# Interfacenopanda.net
KiCad netlist of a schematic drawn in EAGLE
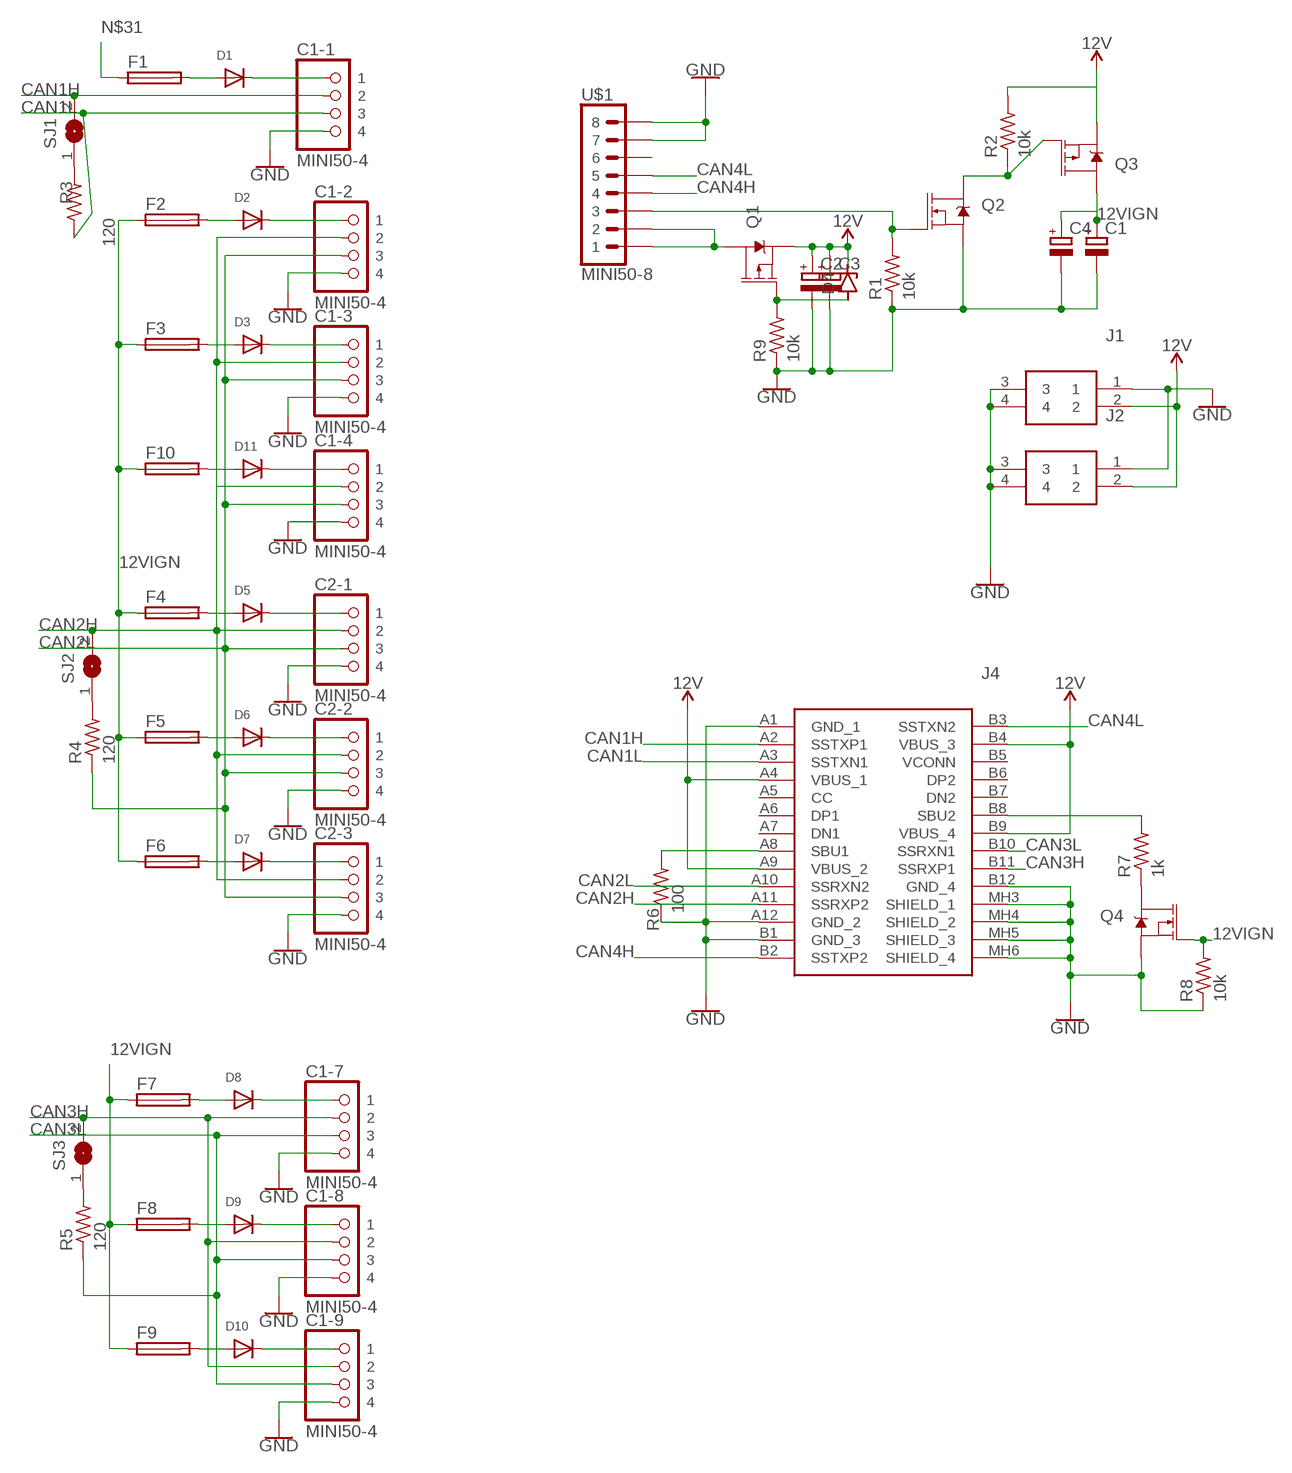
[diagram p0: schematic, sheet 1]

(export (version "E")
  (design (tool "Eeschema 10.0.6"))
  (components
    (comp (ref "C1")
      (value "CPOL-EU153CLV-1010")
      (footprint "eagle-import:153CLV-1010")
      (libsource (lib "eagle-import") (part "CPOL-EU153CLV-1010"))
    )
    (comp (ref "C1-1")
      (value "MINI50-4")
      (footprint "eagle-import:MINI50")
      (libsource (lib "eagle-import") (part "MINI50-4"))
    )
    (comp (ref "C1-2")
      (value "MINI50-4")
      (footprint "eagle-import:MINI50")
      (libsource (lib "eagle-import") (part "MINI50-4"))
    )
    (comp (ref "C1-3")
      (value "MINI50-4")
      (footprint "eagle-import:MINI50")
      (libsource (lib "eagle-import") (part "MINI50-4"))
    )
    (comp (ref "C1-4")
      (value "MINI50-4")
      (footprint "eagle-import:MINI50")
      (libsource (lib "eagle-import") (part "MINI50-4"))
    )
    (comp (ref "C1-7")
      (value "MINI50-4")
      (footprint "eagle-import:MINI50")
      (libsource (lib "eagle-import") (part "MINI50-4"))
    )
    (comp (ref "C1-8")
      (value "MINI50-4")
      (footprint "eagle-import:MINI50")
      (libsource (lib "eagle-import") (part "MINI50-4"))
    )
    (comp (ref "C1-9")
      (value "MINI50-4")
      (footprint "eagle-import:MINI50")
      (libsource (lib "eagle-import") (part "MINI50-4"))
    )
    (comp (ref "C2")
      (value "CPOL-EU153CLV-1010")
      (footprint "eagle-import:153CLV-1010")
      (libsource (lib "eagle-import") (part "CPOL-EU153CLV-1010"))
    )
    (comp (ref "C2-1")
      (value "MINI50-4")
      (footprint "eagle-import:MINI50")
      (libsource (lib "eagle-import") (part "MINI50-4"))
    )
    (comp (ref "C2-2")
      (value "MINI50-4")
      (footprint "eagle-import:MINI50")
      (libsource (lib "eagle-import") (part "MINI50-4"))
    )
    (comp (ref "C2-3")
      (value "MINI50-4")
      (footprint "eagle-import:MINI50")
      (libsource (lib "eagle-import") (part "MINI50-4"))
    )
    (comp (ref "C3")
      (value "CPOL-EU153CLV-0505")
      (footprint "eagle-import:153CLV-0505")
      (libsource (lib "eagle-import") (part "CPOL-EU153CLV-0505"))
    )
    (comp (ref "C4")
      (value "CPOL-EU153CLV-0505")
      (footprint "eagle-import:153CLV-0505")
      (libsource (lib "eagle-import") (part "CPOL-EU153CLV-0505"))
    )
    (comp (ref "D1")
      (value "DIODESOD-323F")
      (footprint "eagle-import:SOD-323F")
      (libsource (lib "eagle-import") (part "DIODESOD-323F"))
    )
    (comp (ref "D2")
      (value "DIODESOD-323F")
      (footprint "eagle-import:SOD-323F")
      (libsource (lib "eagle-import") (part "DIODESOD-323F"))
    )
    (comp (ref "D3")
      (value "DIODESOD-323F")
      (footprint "eagle-import:SOD-323F")
      (libsource (lib "eagle-import") (part "DIODESOD-323F"))
    )
    (comp (ref "D4")
      (value "ZENER_DO-219-AB(SOD123F)")
      (footprint "eagle-import:SODFL3718X115")
      (libsource (lib "eagle-import") (part "ZENERDO-219-AB(SOD123F)_"))
    )
    (comp (ref "D5")
      (value "DIODESOD-323F")
      (footprint "eagle-import:SOD-323F")
      (libsource (lib "eagle-import") (part "DIODESOD-323F"))
    )
    (comp (ref "D6")
      (value "DIODESOD-323F")
      (footprint "eagle-import:SOD-323F")
      (libsource (lib "eagle-import") (part "DIODESOD-323F"))
    )
    (comp (ref "D7")
      (value "DIODESOD-323F")
      (footprint "eagle-import:SOD-323F")
      (libsource (lib "eagle-import") (part "DIODESOD-323F"))
    )
    (comp (ref "D8")
      (value "DIODESOD-323F")
      (footprint "eagle-import:SOD-323F")
      (libsource (lib "eagle-import") (part "DIODESOD-323F"))
    )
    (comp (ref "D9")
      (value "DIODESOD-323F")
      (footprint "eagle-import:SOD-323F")
      (libsource (lib "eagle-import") (part "DIODESOD-323F"))
    )
    (comp (ref "D10")
      (value "DIODESOD-323F")
      (footprint "eagle-import:SOD-323F")
      (libsource (lib "eagle-import") (part "DIODESOD-323F"))
    )
    (comp (ref "D11")
      (value "DIODESOD-323F")
      (footprint "eagle-import:SOD-323F")
      (libsource (lib "eagle-import") (part "DIODESOD-323F"))
    )
    (comp (ref "F1")
      (value "FUSE_CHIP-1206(3216-METRIC)")
      (footprint "eagle-import:FUSC3215X82N")
      (libsource (lib "eagle-import") (part "FUSECHIP-1206(3216-METRIC)_"))
    )
    (comp (ref "F2")
      (value "FUSE_CHIP-1206(3216-METRIC)")
      (footprint "eagle-import:FUSC3215X82N")
      (libsource (lib "eagle-import") (part "FUSECHIP-1206(3216-METRIC)_"))
    )
    (comp (ref "F3")
      (value "FUSE_CHIP-1206(3216-METRIC)")
      (footprint "eagle-import:FUSC3215X82N")
      (libsource (lib "eagle-import") (part "FUSECHIP-1206(3216-METRIC)_"))
    )
    (comp (ref "F4")
      (value "FUSE_CHIP-1206(3216-METRIC)")
      (footprint "eagle-import:FUSC3215X82N")
      (libsource (lib "eagle-import") (part "FUSECHIP-1206(3216-METRIC)_"))
    )
    (comp (ref "F5")
      (value "FUSE_CHIP-1206(3216-METRIC)")
      (footprint "eagle-import:FUSC3215X82N")
      (libsource (lib "eagle-import") (part "FUSECHIP-1206(3216-METRIC)_"))
    )
    (comp (ref "F6")
      (value "FUSE_CHIP-1206(3216-METRIC)")
      (footprint "eagle-import:FUSC3215X82N")
      (libsource (lib "eagle-import") (part "FUSECHIP-1206(3216-METRIC)_"))
    )
    (comp (ref "F7")
      (value "FUSE_CHIP-1206(3216-METRIC)")
      (footprint "eagle-import:FUSC3215X82N")
      (libsource (lib "eagle-import") (part "FUSECHIP-1206(3216-METRIC)_"))
    )
    (comp (ref "F8")
      (value "FUSE_CHIP-1206(3216-METRIC)")
      (footprint "eagle-import:FUSC3215X82N")
      (libsource (lib "eagle-import") (part "FUSECHIP-1206(3216-METRIC)_"))
    )
    (comp (ref "F9")
      (value "FUSE_CHIP-1206(3216-METRIC)")
      (footprint "eagle-import:FUSC3215X82N")
      (libsource (lib "eagle-import") (part "FUSECHIP-1206(3216-METRIC)_"))
    )
    (comp (ref "F10")
      (value "FUSE_CHIP-1206(3216-METRIC)")
      (footprint "eagle-import:FUSC3215X82N")
      (libsource (lib "eagle-import") (part "FUSECHIP-1206(3216-METRIC)_"))
    )
    (comp (ref "J1")
      (value "34912-8020")
      (footprint "eagle-import:0349128020")
      (fields (field (name "MOUSER_PART_NUMBER") "538-34912-8020"))
      (libsource (lib "eagle-import") (part "34912-8020"))
    )
    (comp (ref "J2")
      (value "34912-8020")
      (footprint "eagle-import:0349128020")
      (fields (field (name "MOUSER_PART_NUMBER") "538-34912-8020"))
      (libsource (lib "eagle-import") (part "34912-8020"))
    )
    (comp (ref "J4")
      (value "632722110112")
      (footprint "eagle-import:632722110112")
      (fields (field (name "MOUSER_PART_NUMBER") "710-632722110112"))
      (libsource (lib "eagle-import") (part "632722110112"))
    )
    (comp (ref "Q1")
      (value "6.5A/20V/35mΩ")
      (footprint "eagle-import:SO08")
      (libsource (lib "eagle-import") (part "MOSFET_PCH-KI4435DY"))
    )
    (comp (ref "Q2")
      (value "5.8A/30V/35mΩ")
      (footprint "eagle-import:SOT23-3")
      (libsource (lib "eagle-import") (part "MOSFET-NCH-AO3404A"))
    )
    (comp (ref "Q3")
      (value "6.5A/20V/35mΩ")
      (footprint "eagle-import:SO08")
      (libsource (lib "eagle-import") (part "MOSFET_PCH-KI4435DY"))
    )
    (comp (ref "Q4")
      (value "5.8A/30V/35mΩ")
      (footprint "eagle-import:SOT23-3")
      (libsource (lib "eagle-import") (part "MOSFET-NCH-AO3404A"))
    )
    (comp (ref "R1")
      (value "10k")
      (footprint "eagle-import:0402-R")
      (libsource (lib "eagle-import") (part "R0402"))
    )
    (comp (ref "R2")
      (value "10k")
      (footprint "eagle-import:0402-R")
      (libsource (lib "eagle-import") (part "R0402"))
    )
    (comp (ref "R3")
      (value "120")
      (footprint "eagle-import:0402-R")
      (libsource (lib "eagle-import") (part "R0402"))
    )
    (comp (ref "R4")
      (value "120")
      (footprint "eagle-import:0402-R")
      (libsource (lib "eagle-import") (part "R0402"))
    )
    (comp (ref "R5")
      (value "120")
      (footprint "eagle-import:0402-R")
      (libsource (lib "eagle-import") (part "R0402"))
    )
    (comp (ref "R6")
      (value "100")
      (footprint "eagle-import:0402-R")
      (libsource (lib "eagle-import") (part "R0402"))
    )
    (comp (ref "R7")
      (value "1k")
      (footprint "eagle-import:0402-R")
      (libsource (lib "eagle-import") (part "R0402"))
    )
    (comp (ref "R8")
      (value "10k")
      (footprint "eagle-import:0402-R")
      (libsource (lib "eagle-import") (part "R0402"))
    )
    (comp (ref "R9")
      (value "10k")
      (footprint "eagle-import:0402-R")
      (libsource (lib "eagle-import") (part "R0402"))
    )
    (comp (ref "SJ1") (value "SJ") (footprint "eagle-import:SJ") (libsource (lib "eagle-import") (part "SJ")))
    (comp (ref "SJ2") (value "SJ") (footprint "eagle-import:SJ") (libsource (lib "eagle-import") (part "SJ")))
    (comp (ref "SJ3") (value "SJ") (footprint "eagle-import:SJ") (libsource (lib "eagle-import") (part "SJ")))
    (comp (ref "U$1")
      (value "MINI50-8")
      (footprint "eagle-import:MINI50-8")
      (libsource (lib "eagle-import") (part "MINI50-8"))
    )
  )
  (nets
    (net (code "1") (name "/12VIGN") (class "Default")
      (node (ref "C1") (pin "+") (pinfunction "+_+") (pintype "passive"))
      (node (ref "C4") (pin "+") (pinfunction "+_+") (pintype "passive"))
      (node (ref "F10") (pin "1") (pinfunction "1_1") (pintype "passive"))
      (node (ref "F2") (pin "1") (pinfunction "1_1") (pintype "passive"))
      (node (ref "F3") (pin "1") (pinfunction "1_1") (pintype "passive"))
      (node (ref "F4") (pin "1") (pinfunction "1_1") (pintype "passive"))
      (node (ref "F5") (pin "1") (pinfunction "1_1") (pintype "passive"))
      (node (ref "F6") (pin "1") (pinfunction "1_1") (pintype "passive"))
      (node (ref "F7") (pin "1") (pinfunction "1_1") (pintype "passive"))
      (node (ref "F8") (pin "1") (pinfunction "1_1") (pintype "passive"))
      (node (ref "F9") (pin "1") (pinfunction "1_1") (pintype "passive"))
      (node (ref "Q3") (pin "5") (pinfunction "D_5") (pintype "bidirectional"))
      (node (ref "Q3") (pin "6") (pinfunction "D_6") (pintype "bidirectional"))
      (node (ref "Q3") (pin "7") (pinfunction "D_7") (pintype "bidirectional"))
      (node (ref "Q3") (pin "8") (pinfunction "D_8") (pintype "bidirectional"))
      (node (ref "Q4") (pin "1") (pinfunction "G_1") (pintype "bidirectional"))
      (node (ref "R8") (pin "2") (pinfunction "2_2") (pintype "passive"))
    )
    (net (code "2") (name "/CAN1H") (class "Default")
      (node (ref "C1-1") (pin "3") (pinfunction "2_3") (pintype "passive"))
      (node (ref "J4") (pin "A2") (pinfunction "SSTXP1_A2") (pintype "bidirectional"))
      (node (ref "SJ1") (pin "2") (pinfunction "2_2") (pintype "passive"))
    )
    (net (code "3") (name "/CAN1L") (class "Default")
      (node (ref "C1-1") (pin "2") (pinfunction "3_2") (pintype "passive"))
      (node (ref "J4") (pin "A3") (pinfunction "SSTXN1_A3") (pintype "bidirectional"))
      (node (ref "R3") (pin "1") (pinfunction "1_1") (pintype "passive"))
    )
    (net (code "4") (name "/CAN2H") (class "Default")
      (node (ref "C1-2") (pin "3") (pinfunction "2_3") (pintype "passive"))
      (node (ref "C1-3") (pin "3") (pinfunction "2_3") (pintype "passive"))
      (node (ref "C1-4") (pin "3") (pinfunction "2_3") (pintype "passive"))
      (node (ref "C2-1") (pin "3") (pinfunction "2_3") (pintype "passive"))
      (node (ref "C2-2") (pin "3") (pinfunction "2_3") (pintype "passive"))
      (node (ref "C2-3") (pin "3") (pinfunction "2_3") (pintype "passive"))
      (node (ref "J4") (pin "A11") (pinfunction "SSRXP2_A11") (pintype "bidirectional"))
      (node (ref "SJ2") (pin "2") (pinfunction "2_2") (pintype "passive"))
    )
    (net (code "5") (name "/CAN2L") (class "Default")
      (node (ref "C1-2") (pin "2") (pinfunction "3_2") (pintype "passive"))
      (node (ref "C1-3") (pin "2") (pinfunction "3_2") (pintype "passive"))
      (node (ref "C1-4") (pin "2") (pinfunction "3_2") (pintype "passive"))
      (node (ref "C2-1") (pin "2") (pinfunction "3_2") (pintype "passive"))
      (node (ref "C2-2") (pin "2") (pinfunction "3_2") (pintype "passive"))
      (node (ref "C2-3") (pin "2") (pinfunction "3_2") (pintype "passive"))
      (node (ref "J4") (pin "A10") (pinfunction "SSRXN2_A10") (pintype "bidirectional"))
      (node (ref "R4") (pin "1") (pinfunction "1_1") (pintype "passive"))
    )
    (net (code "6") (name "/CAN3H") (class "Default")
      (node (ref "C1-7") (pin "3") (pinfunction "2_3") (pintype "passive"))
      (node (ref "C1-8") (pin "3") (pinfunction "2_3") (pintype "passive"))
      (node (ref "C1-9") (pin "3") (pinfunction "2_3") (pintype "passive"))
      (node (ref "J4") (pin "B11") (pinfunction "SSRXP1_B11") (pintype "bidirectional"))
      (node (ref "SJ3") (pin "2") (pinfunction "2_2") (pintype "passive"))
    )
    (net (code "7") (name "/CAN3L") (class "Default")
      (node (ref "C1-7") (pin "2") (pinfunction "3_2") (pintype "passive"))
      (node (ref "C1-8") (pin "2") (pinfunction "3_2") (pintype "passive"))
      (node (ref "C1-9") (pin "2") (pinfunction "3_2") (pintype "passive"))
      (node (ref "J4") (pin "B10") (pinfunction "SSRXN1_B10") (pintype "bidirectional"))
      (node (ref "R5") (pin "1") (pinfunction "1_1") (pintype "passive"))
    )
    (net (code "8") (name "/CAN4H") (class "Default")
      (node (ref "J4") (pin "B2") (pinfunction "SSTXP2_B2") (pintype "bidirectional"))
      (node (ref "U$1") (pin "P$4") (pinfunction "4_P$4") (pintype "passive"))
    )
    (net (code "9") (name "/CAN4L") (class "Default")
      (node (ref "J4") (pin "B3") (pinfunction "SSTXN2_B3") (pintype "bidirectional"))
      (node (ref "U$1") (pin "P$5") (pinfunction "5_P$5") (pintype "passive"))
    )
    (net (code "10") (name "/N$31") (class "Default")
      (node (ref "F1") (pin "1") (pinfunction "1_1") (pintype "passive"))
    )
    (net (code "11") (name "12V") (class "Default")
      (node (ref "C2") (pin "+") (pinfunction "+_+") (pintype "passive"))
      (node (ref "C3") (pin "+") (pinfunction "+_+") (pintype "passive"))
      (node (ref "D4") (pin "2") (pinfunction "C_2") (pintype "passive"))
      (node (ref "J1") (pin "2") (pinfunction "2_2") (pintype "bidirectional"))
      (node (ref "J2") (pin "2") (pinfunction "2_2") (pintype "bidirectional"))
      (node (ref "J4") (pin "A4") (pinfunction "VBUS_1_A4") (pintype "bidirectional"))
      (node (ref "J4") (pin "A9") (pinfunction "VBUS_2_A9") (pintype "bidirectional"))
      (node (ref "J4") (pin "B4") (pinfunction "VBUS_3_B4") (pintype "bidirectional"))
      (node (ref "J4") (pin "B9") (pinfunction "VBUS_4_B9") (pintype "bidirectional"))
      (node (ref "Q1") (pin "1") (pinfunction "S_1") (pintype "bidirectional"))
      (node (ref "Q1") (pin "2") (pinfunction "S_2") (pintype "bidirectional"))
      (node (ref "Q1") (pin "3") (pinfunction "S_3") (pintype "bidirectional"))
      (node (ref "Q3") (pin "1") (pinfunction "S_1") (pintype "bidirectional"))
      (node (ref "Q3") (pin "2") (pinfunction "S_2") (pintype "bidirectional"))
      (node (ref "Q3") (pin "3") (pinfunction "S_3") (pintype "bidirectional"))
      (node (ref "R2") (pin "2") (pinfunction "2_2") (pintype "passive"))
    )
    (net (code "12") (name "GND") (class "Default")
      (node (ref "C1") (pin "-") (pinfunction "-_-") (pintype "passive"))
      (node (ref "C1-1") (pin "1") (pinfunction "4_1") (pintype "passive"))
      (node (ref "C1-2") (pin "1") (pinfunction "4_1") (pintype "passive"))
      (node (ref "C1-3") (pin "1") (pinfunction "4_1") (pintype "passive"))
      (node (ref "C1-4") (pin "1") (pinfunction "4_1") (pintype "passive"))
      (node (ref "C1-7") (pin "1") (pinfunction "4_1") (pintype "passive"))
      (node (ref "C1-8") (pin "1") (pinfunction "4_1") (pintype "passive"))
      (node (ref "C1-9") (pin "1") (pinfunction "4_1") (pintype "passive"))
      (node (ref "C2") (pin "-") (pinfunction "-_-") (pintype "passive"))
      (node (ref "C2-1") (pin "1") (pinfunction "4_1") (pintype "passive"))
      (node (ref "C2-2") (pin "1") (pinfunction "4_1") (pintype "passive"))
      (node (ref "C2-3") (pin "1") (pinfunction "4_1") (pintype "passive"))
      (node (ref "C3") (pin "-") (pinfunction "-_-") (pintype "passive"))
      (node (ref "C4") (pin "-") (pinfunction "-_-") (pintype "passive"))
      (node (ref "J1") (pin "1") (pinfunction "1_1") (pintype "bidirectional"))
      (node (ref "J1") (pin "3") (pinfunction "3_3") (pintype "bidirectional"))
      (node (ref "J1") (pin "4") (pinfunction "4_4") (pintype "bidirectional"))
      (node (ref "J2") (pin "1") (pinfunction "1_1") (pintype "bidirectional"))
      (node (ref "J2") (pin "3") (pinfunction "3_3") (pintype "bidirectional"))
      (node (ref "J2") (pin "4") (pinfunction "4_4") (pintype "bidirectional"))
      (node (ref "J4") (pin "A1") (pinfunction "GND_1_A1") (pintype "bidirectional"))
      (node (ref "J4") (pin "A12") (pinfunction "GND_2_A12") (pintype "bidirectional"))
      (node (ref "J4") (pin "B1") (pinfunction "GND_3_B1") (pintype "bidirectional"))
      (node (ref "J4") (pin "B12") (pinfunction "GND_4_B12") (pintype "bidirectional"))
      (node (ref "J4") (pin "MH3") (pinfunction "SHIELD_1_MH3") (pintype "bidirectional"))
      (node (ref "J4") (pin "MH4") (pinfunction "SHIELD_2_MH4") (pintype "bidirectional"))
      (node (ref "J4") (pin "MH5") (pinfunction "SHIELD_3_MH5") (pintype "bidirectional"))
      (node (ref "J4") (pin "MH6") (pinfunction "SHIELD_4_MH6") (pintype "bidirectional"))
      (node (ref "Q2") (pin "2") (pinfunction "S_2") (pintype "bidirectional"))
      (node (ref "Q4") (pin "2") (pinfunction "S_2") (pintype "bidirectional"))
      (node (ref "R1") (pin "1") (pinfunction "1_1") (pintype "passive"))
      (node (ref "R6") (pin "1") (pinfunction "1_1") (pintype "passive"))
      (node (ref "R8") (pin "1") (pinfunction "1_1") (pintype "passive"))
      (node (ref "R9") (pin "1") (pinfunction "1_1") (pintype "passive"))
      (node (ref "U$1") (pin "P$7") (pinfunction "7_P$7") (pintype "passive"))
      (node (ref "U$1") (pin "P$8") (pinfunction "8_P$8") (pintype "passive"))
    )
    (net (code "13") (name "Net-(C1-1-1)") (class "Default")
      (node (ref "C1-1") (pin "4") (pinfunction "1_4") (pintype "passive"))
      (node (ref "D1") (pin "C") (pinfunction "C_C") (pintype "passive"))
    )
    (net (code "14") (name "Net-(C1-2-1)") (class "Default")
      (node (ref "C1-2") (pin "4") (pinfunction "1_4") (pintype "passive"))
      (node (ref "D2") (pin "C") (pinfunction "C_C") (pintype "passive"))
    )
    (net (code "15") (name "Net-(C1-3-1)") (class "Default")
      (node (ref "C1-3") (pin "4") (pinfunction "1_4") (pintype "passive"))
      (node (ref "D3") (pin "C") (pinfunction "C_C") (pintype "passive"))
    )
    (net (code "16") (name "Net-(C1-4-1)") (class "Default")
      (node (ref "C1-4") (pin "4") (pinfunction "1_4") (pintype "passive"))
      (node (ref "D11") (pin "C") (pinfunction "C_C") (pintype "passive"))
    )
    (net (code "17") (name "Net-(C1-7-1)") (class "Default")
      (node (ref "C1-7") (pin "4") (pinfunction "1_4") (pintype "passive"))
      (node (ref "D8") (pin "C") (pinfunction "C_C") (pintype "passive"))
    )
    (net (code "18") (name "Net-(C1-8-1)") (class "Default")
      (node (ref "C1-8") (pin "4") (pinfunction "1_4") (pintype "passive"))
      (node (ref "D9") (pin "C") (pinfunction "C_C") (pintype "passive"))
    )
    (net (code "19") (name "Net-(C1-9-1)") (class "Default")
      (node (ref "C1-9") (pin "4") (pinfunction "1_4") (pintype "passive"))
      (node (ref "D10") (pin "C") (pinfunction "C_C") (pintype "passive"))
    )
    (net (code "20") (name "Net-(C2-1-1)") (class "Default")
      (node (ref "C2-1") (pin "4") (pinfunction "1_4") (pintype "passive"))
      (node (ref "D5") (pin "C") (pinfunction "C_C") (pintype "passive"))
    )
    (net (code "21") (name "Net-(C2-2-1)") (class "Default")
      (node (ref "C2-2") (pin "4") (pinfunction "1_4") (pintype "passive"))
      (node (ref "D6") (pin "C") (pinfunction "C_C") (pintype "passive"))
    )
    (net (code "22") (name "Net-(C2-3-1)") (class "Default")
      (node (ref "C2-3") (pin "4") (pinfunction "1_4") (pintype "passive"))
      (node (ref "D7") (pin "C") (pinfunction "C_C") (pintype "passive"))
    )
    (net (code "23") (name "Net-(D1-PadA)") (class "Default")
      (node (ref "D1") (pin "A") (pinfunction "A_A") (pintype "passive"))
      (node (ref "F1") (pin "2") (pinfunction "2_2") (pintype "passive"))
    )
    (net (code "24") (name "Net-(D2-PadA)") (class "Default")
      (node (ref "D2") (pin "A") (pinfunction "A_A") (pintype "passive"))
      (node (ref "F2") (pin "2") (pinfunction "2_2") (pintype "passive"))
    )
    (net (code "25") (name "Net-(D3-PadA)") (class "Default")
      (node (ref "D3") (pin "A") (pinfunction "A_A") (pintype "passive"))
      (node (ref "F3") (pin "2") (pinfunction "2_2") (pintype "passive"))
    )
    (net (code "26") (name "Net-(D4-A)") (class "Default")
      (node (ref "D4") (pin "1") (pinfunction "A_1") (pintype "passive"))
      (node (ref "Q1") (pin "4") (pinfunction "G_4") (pintype "bidirectional"))
      (node (ref "R9") (pin "2") (pinfunction "2_2") (pintype "passive"))
    )
    (net (code "27") (name "Net-(D5-PadA)") (class "Default")
      (node (ref "D5") (pin "A") (pinfunction "A_A") (pintype "passive"))
      (node (ref "F4") (pin "2") (pinfunction "2_2") (pintype "passive"))
    )
    (net (code "28") (name "Net-(D6-PadA)") (class "Default")
      (node (ref "D6") (pin "A") (pinfunction "A_A") (pintype "passive"))
      (node (ref "F5") (pin "2") (pinfunction "2_2") (pintype "passive"))
    )
    (net (code "29") (name "Net-(D7-PadA)") (class "Default")
      (node (ref "D7") (pin "A") (pinfunction "A_A") (pintype "passive"))
      (node (ref "F6") (pin "2") (pinfunction "2_2") (pintype "passive"))
    )
    (net (code "30") (name "Net-(D8-PadA)") (class "Default")
      (node (ref "D8") (pin "A") (pinfunction "A_A") (pintype "passive"))
      (node (ref "F7") (pin "2") (pinfunction "2_2") (pintype "passive"))
    )
    (net (code "31") (name "Net-(D9-PadA)") (class "Default")
      (node (ref "D9") (pin "A") (pinfunction "A_A") (pintype "passive"))
      (node (ref "F8") (pin "2") (pinfunction "2_2") (pintype "passive"))
    )
    (net (code "32") (name "Net-(D10-PadA)") (class "Default")
      (node (ref "D10") (pin "A") (pinfunction "A_A") (pintype "passive"))
      (node (ref "F9") (pin "2") (pinfunction "2_2") (pintype "passive"))
    )
    (net (code "33") (name "Net-(D11-PadA)") (class "Default")
      (node (ref "D11") (pin "A") (pinfunction "A_A") (pintype "passive"))
      (node (ref "F10") (pin "2") (pinfunction "2_2") (pintype "passive"))
    )
    (net (code "34") (name "Net-(J4-SBU1)") (class "Default")
      (node (ref "J4") (pin "A8") (pinfunction "SBU1_A8") (pintype "bidirectional"))
      (node (ref "R6") (pin "2") (pinfunction "2_2") (pintype "passive"))
    )
    (net (code "35") (name "Net-(J4-SBU2)") (class "Default")
      (node (ref "J4") (pin "B8") (pinfunction "SBU2_B8") (pintype "bidirectional"))
      (node (ref "R7") (pin "2") (pinfunction "2_2") (pintype "passive"))
    )
    (net (code "36") (name "Net-(Q2-D)") (class "Default")
      (node (ref "Q2") (pin "3") (pinfunction "D_3") (pintype "bidirectional"))
      (node (ref "Q3") (pin "4") (pinfunction "G_4") (pintype "bidirectional"))
      (node (ref "R2") (pin "1") (pinfunction "1_1") (pintype "passive"))
    )
    (net (code "37") (name "Net-(Q2-G)") (class "Default")
      (node (ref "Q2") (pin "1") (pinfunction "G_1") (pintype "bidirectional"))
      (node (ref "R1") (pin "2") (pinfunction "2_2") (pintype "passive"))
      (node (ref "U$1") (pin "P$3") (pinfunction "3_P$3") (pintype "passive"))
    )
    (net (code "38") (name "Net-(Q4-D)") (class "Default")
      (node (ref "Q4") (pin "3") (pinfunction "D_3") (pintype "bidirectional"))
      (node (ref "R7") (pin "1") (pinfunction "1_1") (pintype "passive"))
    )
    (net (code "39") (name "Net-(R3-Pad2)") (class "Default")
      (node (ref "R3") (pin "2") (pinfunction "2_2") (pintype "passive"))
      (node (ref "SJ1") (pin "1") (pinfunction "1_1") (pintype "passive"))
    )
    (net (code "40") (name "Net-(R4-Pad2)") (class "Default")
      (node (ref "R4") (pin "2") (pinfunction "2_2") (pintype "passive"))
      (node (ref "SJ2") (pin "1") (pinfunction "1_1") (pintype "passive"))
    )
    (net (code "41") (name "Net-(R5-Pad2)") (class "Default")
      (node (ref "R5") (pin "2") (pinfunction "2_2") (pintype "passive"))
      (node (ref "SJ3") (pin "1") (pinfunction "1_1") (pintype "passive"))
    )
    (net (code "42") (name "Net-(U$1-1)") (class "Default")
      (node (ref "Q1") (pin "5") (pinfunction "D_5") (pintype "bidirectional"))
      (node (ref "Q1") (pin "6") (pinfunction "D_6") (pintype "bidirectional"))
      (node (ref "Q1") (pin "7") (pinfunction "D_7") (pintype "bidirectional"))
      (node (ref "Q1") (pin "8") (pinfunction "D_8") (pintype "bidirectional"))
      (node (ref "U$1") (pin "P$1") (pinfunction "1_P$1") (pintype "passive"))
      (node (ref "U$1") (pin "P$2") (pinfunction "2_P$2") (pintype "passive"))
    )
    (net (code "43") (name "unconnected-(J4-CC-PadA5)") (class "Default")
      (node (ref "J4") (pin "A5") (pinfunction "CC_A5") (pintype "bidirectional"))
    )
    (net (code "44") (name "unconnected-(J4-DN1-PadA7)") (class "Default")
      (node (ref "J4") (pin "A7") (pinfunction "DN1_A7") (pintype "bidirectional"))
    )
    (net (code "45") (name "unconnected-(J4-DN2-PadB7)") (class "Default")
      (node (ref "J4") (pin "B7") (pinfunction "DN2_B7") (pintype "bidirectional"))
    )
    (net (code "46") (name "unconnected-(J4-DP1-PadA6)") (class "Default")
      (node (ref "J4") (pin "A6") (pinfunction "DP1_A6") (pintype "bidirectional"))
    )
    (net (code "47") (name "unconnected-(J4-DP2-PadB6)") (class "Default")
      (node (ref "J4") (pin "B6") (pinfunction "DP2_B6") (pintype "bidirectional"))
    )
    (net (code "48") (name "unconnected-(J4-VCONN-PadB5)") (class "Default")
      (node (ref "J4") (pin "B5") (pinfunction "VCONN_B5") (pintype "bidirectional"))
    )
    (net (code "49") (name "unconnected-(U$1-6-PadP$6)") (class "Default")
      (node (ref "U$1") (pin "P$6") (pinfunction "6_P$6") (pintype "passive"))
    )
  )
)
